# grizzly_bear_revF.net
KiCad netlist of a schematic drawn in EAGLE
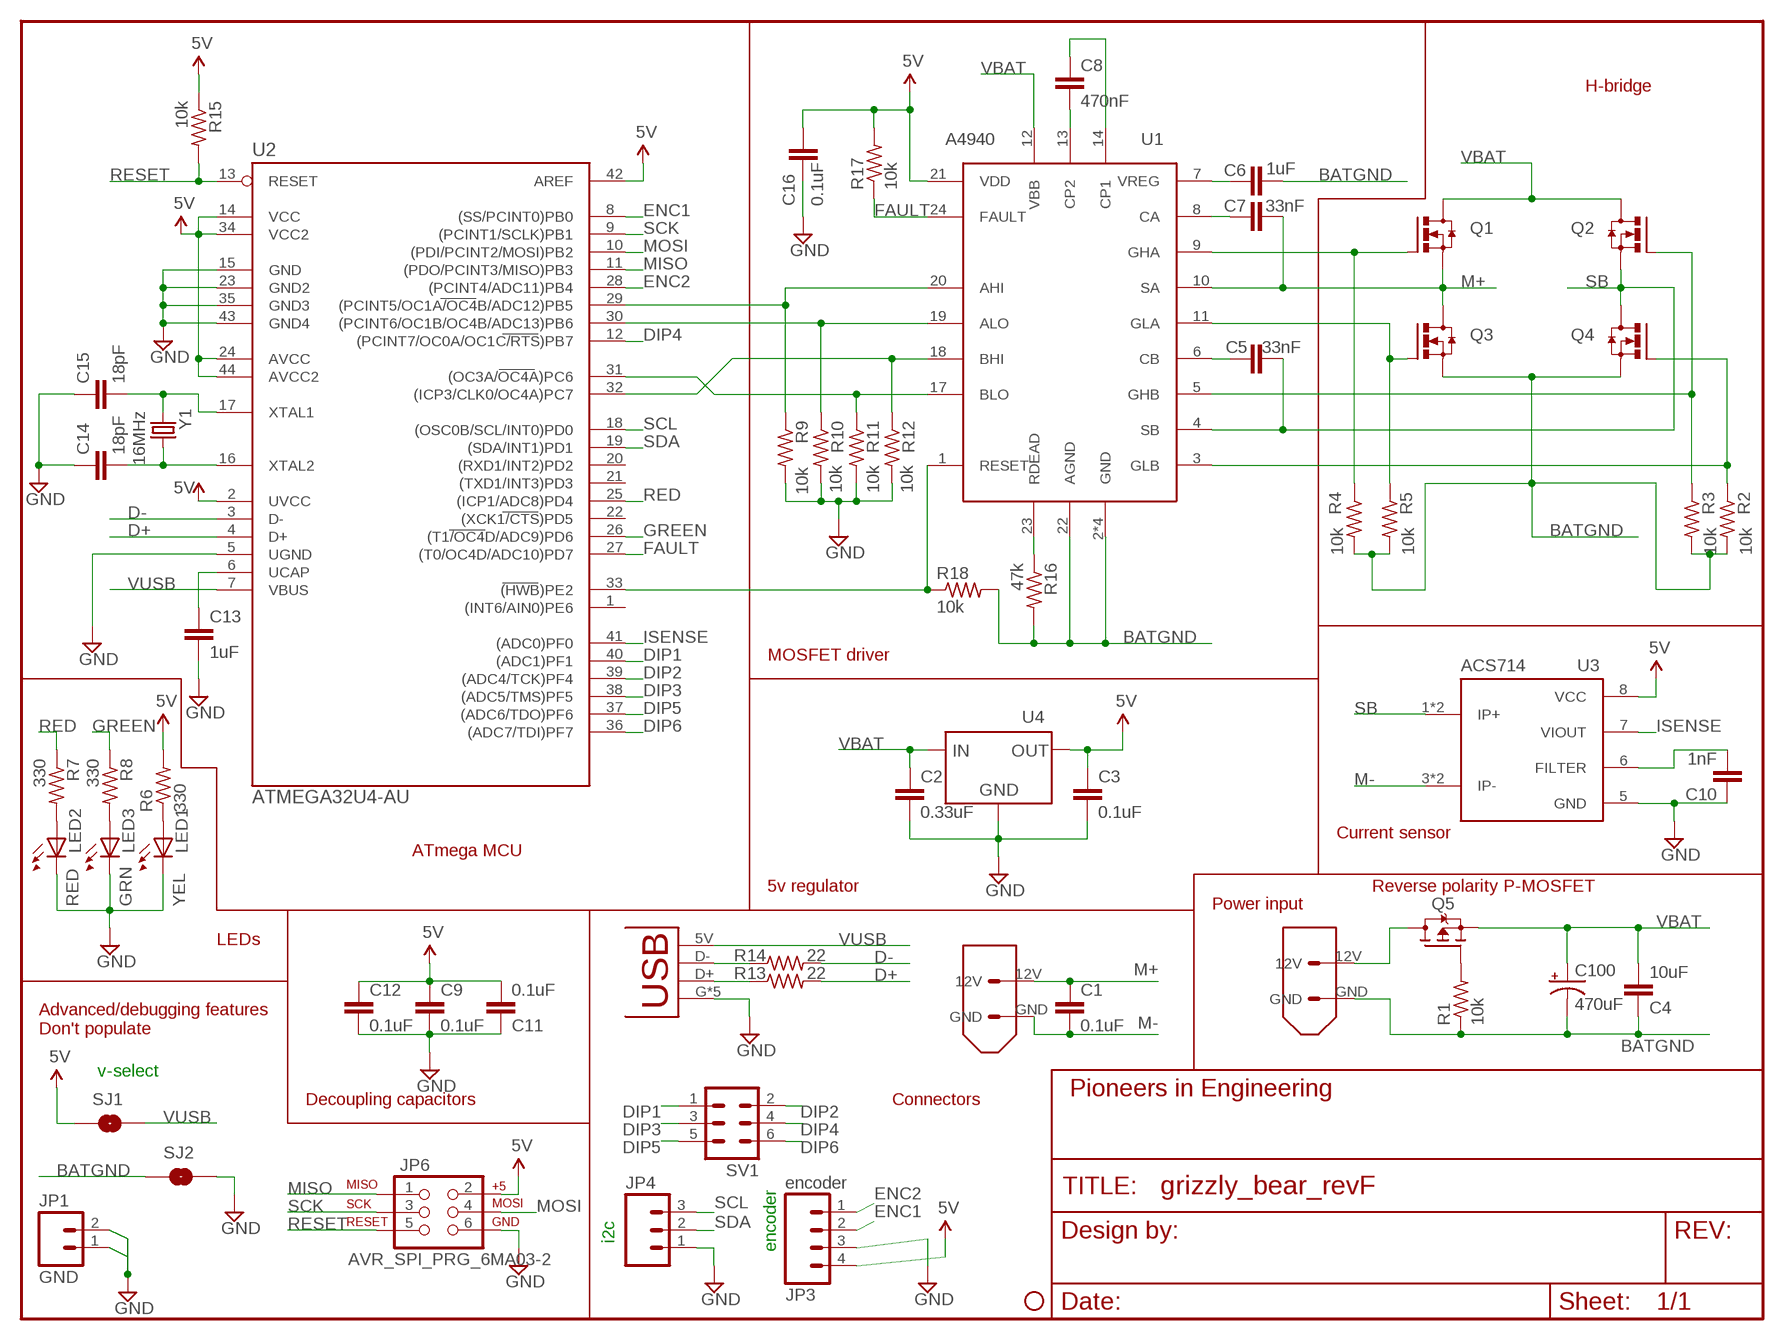
[diagram p0: schematic, sheet 1]

(export (version "E")
  (design (tool "Eeschema 10.0.6"))
  (components
    (comp (ref "C1")
      (value "0.1uF")
      (footprint "eagle-import:0603-CAP")
      (libsource (lib "eagle-import") (part "CAP0603-CAP"))
    )
    (comp (ref "C2")
      (value "0.33uF")
      (footprint "eagle-import:0603-CAP")
      (libsource (lib "eagle-import") (part "CAP0603-CAP"))
    )
    (comp (ref "C3")
      (value "0.1uF")
      (footprint "eagle-import:0603-CAP")
      (libsource (lib "eagle-import") (part "CAP0603-CAP"))
    )
    (comp (ref "C4")
      (value "10uF")
      (footprint "eagle-import:0603-CAP")
      (libsource (lib "eagle-import") (part "CAP0603-CAP"))
    )
    (comp (ref "C5")
      (value "33nF")
      (footprint "eagle-import:0603-CAP")
      (libsource (lib "eagle-import") (part "CAP0603-CAP"))
    )
    (comp (ref "C6")
      (value "1uF")
      (footprint "eagle-import:0603-CAP")
      (libsource (lib "eagle-import") (part "CAP0603-CAP"))
    )
    (comp (ref "C7")
      (value "33nF")
      (footprint "eagle-import:0603-CAP")
      (libsource (lib "eagle-import") (part "CAP0603-CAP"))
    )
    (comp (ref "C8")
      (value "470nF")
      (footprint "eagle-import:0603-CAP")
      (libsource (lib "eagle-import") (part "CAP0603-CAP"))
    )
    (comp (ref "C9")
      (value "0.1uF")
      (footprint "eagle-import:0603-CAP")
      (libsource (lib "eagle-import") (part "CAP0603-CAP"))
    )
    (comp (ref "C10")
      (value "1nF")
      (footprint "eagle-import:0603-CAP")
      (libsource (lib "eagle-import") (part "CAP0603-CAP"))
    )
    (comp (ref "C11")
      (value "0.1uF")
      (footprint "eagle-import:0603-CAP")
      (libsource (lib "eagle-import") (part "CAP0603-CAP"))
    )
    (comp (ref "C12")
      (value "0.1uF")
      (footprint "eagle-import:0603-CAP")
      (libsource (lib "eagle-import") (part "CAP0603-CAP"))
    )
    (comp (ref "C13")
      (value "1uF")
      (footprint "eagle-import:0603-CAP")
      (libsource (lib "eagle-import") (part "CAP0603-CAP"))
    )
    (comp (ref "C14")
      (value "18pF")
      (footprint "eagle-import:0603-CAP")
      (libsource (lib "eagle-import") (part "CAP0603-CAP"))
    )
    (comp (ref "C15")
      (value "18pF")
      (footprint "eagle-import:0603-CAP")
      (libsource (lib "eagle-import") (part "CAP0603-CAP"))
    )
    (comp (ref "C16")
      (value "0.1uF")
      (footprint "eagle-import:0603-CAP")
      (libsource (lib "eagle-import") (part "CAP0603-CAP"))
    )
    (comp (ref "C100")
      (value "470uF")
      (footprint "eagle-import:PANASONIC_G")
      (libsource (lib "eagle-import") (part "CAP_POLG"))
    )
    (comp (ref "JP1")
      (value "GND")
      (footprint "eagle-import:1X02")
      (libsource (lib "eagle-import") (part "M02PTH"))
    )
    (comp (ref "JP3")
      (value "encoder")
      (footprint "eagle-import:1X04-MTA")
      (fields (field (name "PARTNUMBER") "A1922-ND"))
      (libsource (lib "eagle-import") (part "M041X04-MTA"))
    )
    (comp (ref "JP4")
      (value "M031X03-MTA")
      (footprint "eagle-import:1X03-MTA")
      (fields (field (name "PARTNUMBER") "A19470-ND"))
      (libsource (lib "eagle-import") (part "M031X03-MTA"))
    )
    (comp (ref "JP6")
      (value "AVR_SPI_PRG_6MA03-2")
      (footprint "eagle-import:MA03-2")
      (libsource (lib "eagle-import") (part "AVR_SPI_PRG_6MA03-2"))
    )
    (comp (ref "LED1")
      (value "YEL")
      (footprint "eagle-import:LED-0805")
      (libsource (lib "eagle-import") (part "LED0805"))
    )
    (comp (ref "LED2")
      (value "RED")
      (footprint "eagle-import:LED-0805")
      (libsource (lib "eagle-import") (part "LED0805"))
    )
    (comp (ref "LED3")
      (value "GRN")
      (footprint "eagle-import:LED-0805")
      (libsource (lib "eagle-import") (part "LED0805"))
    )
    (comp (ref "Q1")
      (value "N-CHANNEL-MOSFET")
      (footprint "eagle-import:SOT669")
      (libsource (lib "eagle-import") (part "N-CHANNEL-MOSFET"))
    )
    (comp (ref "Q2")
      (value "N-CHANNEL-MOSFET")
      (footprint "eagle-import:SOT669")
      (libsource (lib "eagle-import") (part "N-CHANNEL-MOSFET"))
    )
    (comp (ref "Q3")
      (value "N-CHANNEL-MOSFET")
      (footprint "eagle-import:SOT669")
      (libsource (lib "eagle-import") (part "N-CHANNEL-MOSFET"))
    )
    (comp (ref "Q4")
      (value "N-CHANNEL-MOSFET")
      (footprint "eagle-import:SOT669")
      (libsource (lib "eagle-import") (part "N-CHANNEL-MOSFET"))
    )
    (comp (ref "Q5")
      (value "IPD90P03P4L")
      (footprint "eagle-import:TO252")
      (libsource (lib "eagle-import") (part "P-CHANNEL-MOSFETTO252"))
    )
    (comp (ref "R1")
      (value "10k")
      (footprint "eagle-import:R0603")
      (libsource (lib "eagle-import") (part "R-US_R0603"))
    )
    (comp (ref "R2")
      (value "10k")
      (footprint "eagle-import:R0603")
      (libsource (lib "eagle-import") (part "R-US_R0603"))
    )
    (comp (ref "R3")
      (value "10k")
      (footprint "eagle-import:R0603")
      (libsource (lib "eagle-import") (part "R-US_R0603"))
    )
    (comp (ref "R4")
      (value "10k")
      (footprint "eagle-import:R0603")
      (libsource (lib "eagle-import") (part "R-US_R0603"))
    )
    (comp (ref "R5")
      (value "10k")
      (footprint "eagle-import:R0603")
      (libsource (lib "eagle-import") (part "R-US_R0603"))
    )
    (comp (ref "R6")
      (value "330")
      (footprint "eagle-import:R0603")
      (libsource (lib "eagle-import") (part "R-US_R0603"))
    )
    (comp (ref "R7")
      (value "330")
      (footprint "eagle-import:R0603")
      (libsource (lib "eagle-import") (part "R-US_R0603"))
    )
    (comp (ref "R8")
      (value "330")
      (footprint "eagle-import:R0603")
      (libsource (lib "eagle-import") (part "R-US_R0603"))
    )
    (comp (ref "R9")
      (value "10k")
      (footprint "eagle-import:R0603")
      (libsource (lib "eagle-import") (part "R-US_R0603"))
    )
    (comp (ref "R10")
      (value "10k")
      (footprint "eagle-import:R0603")
      (libsource (lib "eagle-import") (part "R-US_R0603"))
    )
    (comp (ref "R11")
      (value "10k")
      (footprint "eagle-import:R0603")
      (libsource (lib "eagle-import") (part "R-US_R0603"))
    )
    (comp (ref "R12")
      (value "10k")
      (footprint "eagle-import:R0603")
      (libsource (lib "eagle-import") (part "R-US_R0603"))
    )
    (comp (ref "R13")
      (value "22")
      (footprint "eagle-import:R0603")
      (libsource (lib "eagle-import") (part "R-US_R0603"))
    )
    (comp (ref "R14")
      (value "22")
      (footprint "eagle-import:R0603")
      (libsource (lib "eagle-import") (part "R-US_R0603"))
    )
    (comp (ref "R15")
      (value "10k")
      (footprint "eagle-import:R0603")
      (libsource (lib "eagle-import") (part "R-US_R0603"))
    )
    (comp (ref "R16")
      (value "47k")
      (footprint "eagle-import:R0603")
      (libsource (lib "eagle-import") (part "R-US_R0603"))
    )
    (comp (ref "R17")
      (value "10k")
      (footprint "eagle-import:R0603")
      (libsource (lib "eagle-import") (part "R-US_R0603"))
    )
    (comp (ref "R18")
      (value "10k")
      (footprint "eagle-import:R0603")
      (libsource (lib "eagle-import") (part "R-US_R0603"))
    )
    (comp (ref "SJ1")
      (value "SOLDERJUMPERNO")
      (footprint "eagle-import:SJ_2S-NO")
      (libsource (lib "eagle-import") (part "SOLDERJUMPERNO"))
    )
    (comp (ref "SJ2")
      (value "SOLDERJUMPERNO")
      (footprint "eagle-import:SJ_2S-NO")
      (libsource (lib "eagle-import") (part "SOLDERJUMPERNO"))
    )
    (comp (ref "STANDOFF4")
      (value "STAND-OFF")
      (footprint "eagle-import:STAND-OFF")
      (libsource (lib "eagle-import") (part "STAND-OFF"))
    )
    (comp (ref "SV1")
      (value "MA03-2")
      (footprint "eagle-import:MA03-2")
      (libsource (lib "eagle-import") (part "MA03-2"))
    )
    (comp (ref "U$2")
      (value "USB-M26FTR")
      (footprint "eagle-import:USB-M26FTR")
      (libsource (lib "eagle-import") (part "USB-M26FTR"))
    )
    (comp (ref "U$18")
      (value "XT60CONNECTOR")
      (footprint "eagle-import:XT60CONNECTOR")
      (fields (field (name "PARTNUMBER") "PRT-10474 "))
      (libsource (lib "eagle-import") (part "XT60CONNECTOR"))
    )
    (comp (ref "U$19")
      (value "XT60CONNECTOR")
      (footprint "eagle-import:XT60CONNECTOR")
      (fields (field (name "PARTNUMBER") "PRT-10474 "))
      (libsource (lib "eagle-import") (part "XT60CONNECTOR"))
    )
    (comp (ref "U1")
      (value "A4940")
      (footprint "eagle-import:24-PIN_TSSOP")
      (libsource (lib "eagle-import") (part "A4940"))
    )
    (comp (ref "U2")
      (value "ATMEGA32U4-AU")
      (footprint "eagle-import:TQFP44")
      (libsource (lib "eagle-import") (part "ATMEGA32U4-AU"))
    )
    (comp (ref "U3")
      (value "ACS714")
      (footprint "eagle-import:8-PIN_SOIC")
      (libsource (lib "eagle-import") (part "ACS714"))
    )
    (comp (ref "U4")
      (value "UA78L00")
      (footprint "eagle-import:SOT-89-3")
      (libsource (lib "eagle-import") (part "UA78L00"))
    )
    (comp (ref "Y1")
      (value "16MHz")
      (footprint "eagle-import:HC49UP")
      (libsource (lib "eagle-import") (part "CRYSTALSMD"))
    )
  )
  (nets
    (net (code "1") (name "/BATGND") (class "Default")
      (node (ref "C100") (pin "-") (pinfunction "-_-") (pintype "passive"))
      (node (ref "C4") (pin "1") (pinfunction "1_1") (pintype "passive"))
      (node (ref "C6") (pin "2") (pinfunction "2_2") (pintype "passive"))
      (node (ref "Q3") (pin "1") (pinfunction "S_1") (pintype "passive"))
      (node (ref "Q3") (pin "2") (pinfunction "S_2") (pintype "passive"))
      (node (ref "Q3") (pin "3") (pinfunction "S_3") (pintype "passive"))
      (node (ref "Q4") (pin "1") (pinfunction "S_1") (pintype "passive"))
      (node (ref "Q4") (pin "2") (pinfunction "S_2") (pintype "passive"))
      (node (ref "Q4") (pin "3") (pinfunction "S_3") (pintype "passive"))
      (node (ref "R1") (pin "1") (pinfunction "1_1") (pintype "passive"))
      (node (ref "R16") (pin "2") (pinfunction "2_2") (pintype "passive"))
      (node (ref "R18") (pin "2") (pinfunction "2_2") (pintype "passive"))
      (node (ref "R2") (pin "2") (pinfunction "2_2") (pintype "passive"))
      (node (ref "R3") (pin "2") (pinfunction "2_2") (pintype "passive"))
      (node (ref "R4") (pin "2") (pinfunction "2_2") (pintype "passive"))
      (node (ref "R5") (pin "2") (pinfunction "2_2") (pintype "passive"))
      (node (ref "SJ2") (pin "1") (pinfunction "1_1") (pintype "passive"))
      (node (ref "U$18") (pin "GND") (pinfunction "GND_GND") (pintype "bidirectional"))
      (node (ref "U1") (pin "15") (pinfunction "GND_15") (pintype "bidirectional"))
      (node (ref "U1") (pin "16") (pinfunction "GND_16") (pintype "bidirectional"))
      (node (ref "U1") (pin "2") (pinfunction "GND_2") (pintype "bidirectional"))
      (node (ref "U1") (pin "22") (pinfunction "AGND_22") (pintype "bidirectional"))
      (node (ref "U1") (pin "PAD") (pinfunction "GND_PAD") (pintype "bidirectional"))
    )
    (net (code "2") (name "/D+") (class "Default")
      (node (ref "R13") (pin "2") (pinfunction "2_2") (pintype "passive"))
      (node (ref "U2") (pin "4") (pinfunction "D+_4") (pintype "bidirectional"))
    )
    (net (code "3") (name "/D-") (class "Default")
      (node (ref "R14") (pin "2") (pinfunction "2_2") (pintype "passive"))
      (node (ref "U2") (pin "3") (pinfunction "D-_3") (pintype "bidirectional"))
    )
    (net (code "4") (name "/DIP1") (class "Default")
      (node (ref "SV1") (pin "1") (pinfunction "1_1") (pintype "passive"))
      (node (ref "U2") (pin "40") (pinfunction "(ADC1)PF1_40") (pintype "bidirectional"))
    )
    (net (code "5") (name "/DIP2") (class "Default")
      (node (ref "SV1") (pin "2") (pinfunction "2_2") (pintype "passive"))
      (node (ref "U2") (pin "39") (pinfunction "(ADC4/TCK)PF4_39") (pintype "bidirectional"))
    )
    (net (code "6") (name "/DIP3") (class "Default")
      (node (ref "SV1") (pin "3") (pinfunction "3_3") (pintype "passive"))
      (node (ref "U2") (pin "38") (pinfunction "(ADC5/TMS)PF5_38") (pintype "bidirectional"))
    )
    (net (code "7") (name "/DIP4") (class "Default")
      (node (ref "SV1") (pin "4") (pinfunction "4_4") (pintype "passive"))
      (node (ref "U2") (pin "12") (pinfunction "(PCINT7/OC0A/OC1C/RTS)PB7_12") (pintype "bidirectional"))
    )
    (net (code "8") (name "/DIP5") (class "Default")
      (node (ref "SV1") (pin "5") (pinfunction "5_5") (pintype "passive"))
      (node (ref "U2") (pin "37") (pinfunction "(ADC6/TDO)PF6_37") (pintype "bidirectional"))
    )
    (net (code "9") (name "/DIP6") (class "Default")
      (node (ref "SV1") (pin "6") (pinfunction "6_6") (pintype "passive"))
      (node (ref "U2") (pin "36") (pinfunction "(ADC7/TDI)PF7_36") (pintype "bidirectional"))
    )
    (net (code "10") (name "/ENC1") (class "Default")
      (node (ref "JP3") (pin "2") (pinfunction "2_2") (pintype "passive"))
      (node (ref "U2") (pin "8") (pinfunction "(SS/PCINT0)PB0_8") (pintype "bidirectional"))
    )
    (net (code "11") (name "/ENC2") (class "Default")
      (node (ref "JP3") (pin "1") (pinfunction "1_1") (pintype "passive"))
      (node (ref "U2") (pin "28") (pinfunction "(PCINT4/ADC11)PB4_28") (pintype "bidirectional"))
    )
    (net (code "12") (name "/FAULT") (class "Default")
      (node (ref "R17") (pin "1") (pinfunction "1_1") (pintype "passive"))
      (node (ref "U1") (pin "24") (pinfunction "FAULT_24") (pintype "bidirectional"))
      (node (ref "U2") (pin "27") (pinfunction "(T0/OC4D/ADC10)PD7_27") (pintype "bidirectional"))
    )
    (net (code "13") (name "/GREEN") (class "Default")
      (node (ref "R8") (pin "1") (pinfunction "1_1") (pintype "passive"))
      (node (ref "U2") (pin "26") (pinfunction "(T1/OC4D/ADC9)PD6_26") (pintype "bidirectional"))
    )
    (net (code "14") (name "/ISENSE") (class "Default")
      (node (ref "U2") (pin "41") (pinfunction "(ADC0)PF0_41") (pintype "bidirectional"))
      (node (ref "U3") (pin "7") (pinfunction "VIOUT_7") (pintype "bidirectional"))
    )
    (net (code "15") (name "/M+") (class "Default")
      (node (ref "C1") (pin "1") (pinfunction "1_1") (pintype "passive"))
      (node (ref "C7") (pin "2") (pinfunction "2_2") (pintype "passive"))
      (node (ref "Q1") (pin "1") (pinfunction "S_1") (pintype "passive"))
      (node (ref "Q1") (pin "2") (pinfunction "S_2") (pintype "passive"))
      (node (ref "Q1") (pin "3") (pinfunction "S_3") (pintype "passive"))
      (node (ref "Q3") (pin "MB") (pinfunction "D_MB") (pintype "passive"))
      (node (ref "U$19") (pin "12V") (pinfunction "12V_12V") (pintype "bidirectional"))
      (node (ref "U1") (pin "10") (pinfunction "SA_10") (pintype "bidirectional"))
    )
    (net (code "16") (name "/M-") (class "Default")
      (node (ref "C1") (pin "2") (pinfunction "2_2") (pintype "passive"))
      (node (ref "U$19") (pin "GND") (pinfunction "GND_GND") (pintype "bidirectional"))
      (node (ref "U3") (pin "3") (pinfunction "IP-_3") (pintype "bidirectional"))
      (node (ref "U3") (pin "4") (pinfunction "IP-_4") (pintype "bidirectional"))
    )
    (net (code "17") (name "/MISO") (class "Default")
      (node (ref "JP6") (pin "1") (pinfunction "1_1") (pintype "passive"))
      (node (ref "U2") (pin "11") (pinfunction "(PDO/PCINT3/MISO)PB3_11") (pintype "bidirectional"))
    )
    (net (code "18") (name "/MOSI") (class "Default")
      (node (ref "JP6") (pin "4") (pinfunction "4_4") (pintype "passive"))
      (node (ref "U2") (pin "10") (pinfunction "(PDI/PCINT2/MOSI)PB2_10") (pintype "bidirectional"))
    )
    (net (code "19") (name "/RED") (class "Default")
      (node (ref "R7") (pin "1") (pinfunction "1_1") (pintype "passive"))
      (node (ref "U2") (pin "25") (pinfunction "(ICP1/ADC8)PD4_25") (pintype "bidirectional"))
    )
    (net (code "20") (name "/RESET") (class "Default")
      (node (ref "JP6") (pin "5") (pinfunction "5_5") (pintype "passive"))
      (node (ref "R15") (pin "2") (pinfunction "2_2") (pintype "passive"))
      (node (ref "U2") (pin "13") (pinfunction "RESET_13") (pintype "bidirectional"))
    )
    (net (code "21") (name "/SB") (class "Default")
      (node (ref "C5") (pin "1") (pinfunction "1_1") (pintype "passive"))
      (node (ref "Q2") (pin "1") (pinfunction "S_1") (pintype "passive"))
      (node (ref "Q2") (pin "2") (pinfunction "S_2") (pintype "passive"))
      (node (ref "Q2") (pin "3") (pinfunction "S_3") (pintype "passive"))
      (node (ref "Q4") (pin "MB") (pinfunction "D_MB") (pintype "passive"))
      (node (ref "U1") (pin "4") (pinfunction "SB_4") (pintype "bidirectional"))
      (node (ref "U3") (pin "1") (pinfunction "IP+_1") (pintype "bidirectional"))
      (node (ref "U3") (pin "2") (pinfunction "IP+_2") (pintype "bidirectional"))
    )
    (net (code "22") (name "/SCK") (class "Default")
      (node (ref "JP6") (pin "3") (pinfunction "3_3") (pintype "passive"))
      (node (ref "U2") (pin "9") (pinfunction "(PCINT1/SCLK)PB1_9") (pintype "bidirectional"))
    )
    (net (code "23") (name "/SCL") (class "Default")
      (node (ref "JP4") (pin "3") (pinfunction "3_3") (pintype "passive"))
      (node (ref "U2") (pin "18") (pinfunction "(OSC0B/SCL/INT0)PD0_18") (pintype "bidirectional"))
    )
    (net (code "24") (name "/SDA") (class "Default")
      (node (ref "JP4") (pin "2") (pinfunction "2_2") (pintype "passive"))
      (node (ref "U2") (pin "19") (pinfunction "(SDA/INT1)PD1_19") (pintype "bidirectional"))
    )
    (net (code "25") (name "/VBAT") (class "Default")
      (node (ref "C100") (pin "+") (pinfunction "+_+") (pintype "passive"))
      (node (ref "C2") (pin "1") (pinfunction "1_1") (pintype "passive"))
      (node (ref "C4") (pin "2") (pinfunction "2_2") (pintype "passive"))
      (node (ref "Q1") (pin "MB") (pinfunction "D_MB") (pintype "passive"))
      (node (ref "Q2") (pin "MB") (pinfunction "D_MB") (pintype "passive"))
      (node (ref "Q5") (pin "2") (pinfunction "S_2") (pintype "passive"))
      (node (ref "U1") (pin "12") (pinfunction "VBB_12") (pintype "bidirectional"))
      (node (ref "U4") (pin "INPUT") (pinfunction "IN_INPUT") (pintype "bidirectional"))
    )
    (net (code "26") (name "/VUSB") (class "Default")
      (node (ref "SJ1") (pin "2") (pinfunction "2_2") (pintype "passive"))
      (node (ref "U$2") (pin "5V") (pinfunction "5V_5V") (pintype "bidirectional"))
      (node (ref "U2") (pin "7") (pinfunction "VBUS_7") (pintype "bidirectional"))
    )
    (net (code "27") (name "5V") (class "Default")
      (node (ref "C11") (pin "2") (pinfunction "2_2") (pintype "passive"))
      (node (ref "C12") (pin "1") (pinfunction "1_1") (pintype "passive"))
      (node (ref "C16") (pin "1") (pinfunction "1_1") (pintype "passive"))
      (node (ref "C3") (pin "1") (pinfunction "1_1") (pintype "passive"))
      (node (ref "C9") (pin "1") (pinfunction "1_1") (pintype "passive"))
      (node (ref "JP3") (pin "4") (pinfunction "4_4") (pintype "passive"))
      (node (ref "JP6") (pin "2") (pinfunction "2_2") (pintype "passive"))
      (node (ref "R15") (pin "1") (pinfunction "1_1") (pintype "passive"))
      (node (ref "R17") (pin "2") (pinfunction "2_2") (pintype "passive"))
      (node (ref "R6") (pin "2") (pinfunction "2_2") (pintype "passive"))
      (node (ref "SJ1") (pin "1") (pinfunction "1_1") (pintype "passive"))
      (node (ref "U1") (pin "21") (pinfunction "VDD_21") (pintype "bidirectional"))
      (node (ref "U2") (pin "14") (pinfunction "VCC_14") (pintype "bidirectional"))
      (node (ref "U2") (pin "2") (pinfunction "UVCC_2") (pintype "bidirectional"))
      (node (ref "U2") (pin "24") (pinfunction "AVCC_24") (pintype "bidirectional"))
      (node (ref "U2") (pin "34") (pinfunction "VCC2_34") (pintype "bidirectional"))
      (node (ref "U2") (pin "42") (pinfunction "AREF_42") (pintype "bidirectional"))
      (node (ref "U2") (pin "44") (pinfunction "AVCC2_44") (pintype "bidirectional"))
      (node (ref "U3") (pin "8") (pinfunction "VCC_8") (pintype "bidirectional"))
      (node (ref "U4") (pin "OUTPUT") (pinfunction "OUT_OUTPUT") (pintype "bidirectional"))
    )
    (net (code "28") (name "GND") (class "Default")
      (node (ref "C10") (pin "1") (pinfunction "1_1") (pintype "passive"))
      (node (ref "C11") (pin "1") (pinfunction "1_1") (pintype "passive"))
      (node (ref "C12") (pin "2") (pinfunction "2_2") (pintype "passive"))
      (node (ref "C13") (pin "2") (pinfunction "2_2") (pintype "passive"))
      (node (ref "C14") (pin "1") (pinfunction "1_1") (pintype "passive"))
      (node (ref "C15") (pin "1") (pinfunction "1_1") (pintype "passive"))
      (node (ref "C16") (pin "2") (pinfunction "2_2") (pintype "passive"))
      (node (ref "C2") (pin "2") (pinfunction "2_2") (pintype "passive"))
      (node (ref "C3") (pin "2") (pinfunction "2_2") (pintype "passive"))
      (node (ref "C9") (pin "2") (pinfunction "2_2") (pintype "passive"))
      (node (ref "JP1") (pin "1") (pinfunction "1_1") (pintype "passive"))
      (node (ref "JP1") (pin "2") (pinfunction "2_2") (pintype "passive"))
      (node (ref "JP3") (pin "3") (pinfunction "3_3") (pintype "passive"))
      (node (ref "JP4") (pin "1") (pinfunction "1_1") (pintype "passive"))
      (node (ref "JP6") (pin "6") (pinfunction "6_6") (pintype "passive"))
      (node (ref "LED1") (pin "C") (pinfunction "C_C") (pintype "passive"))
      (node (ref "LED2") (pin "C") (pinfunction "C_C") (pintype "passive"))
      (node (ref "LED3") (pin "C") (pinfunction "C_C") (pintype "passive"))
      (node (ref "R10") (pin "2") (pinfunction "2_2") (pintype "passive"))
      (node (ref "R11") (pin "2") (pinfunction "2_2") (pintype "passive"))
      (node (ref "R12") (pin "2") (pinfunction "2_2") (pintype "passive"))
      (node (ref "R9") (pin "2") (pinfunction "2_2") (pintype "passive"))
      (node (ref "SJ2") (pin "2") (pinfunction "2_2") (pintype "passive"))
      (node (ref "U$2") (pin "G") (pinfunction "G_G") (pintype "bidirectional"))
      (node (ref "U$2") (pin "S1") (pinfunction "G_S1") (pintype "bidirectional"))
      (node (ref "U$2") (pin "S2") (pinfunction "G_S2") (pintype "bidirectional"))
      (node (ref "U$2") (pin "S3") (pinfunction "G_S3") (pintype "bidirectional"))
      (node (ref "U$2") (pin "S4") (pinfunction "G_S4") (pintype "bidirectional"))
      (node (ref "U2") (pin "15") (pinfunction "GND_15") (pintype "bidirectional"))
      (node (ref "U2") (pin "23") (pinfunction "GND2_23") (pintype "bidirectional"))
      (node (ref "U2") (pin "35") (pinfunction "GND3_35") (pintype "bidirectional"))
      (node (ref "U2") (pin "43") (pinfunction "GND4_43") (pintype "bidirectional"))
      (node (ref "U2") (pin "5") (pinfunction "UGND_5") (pintype "bidirectional"))
      (node (ref "U3") (pin "5") (pinfunction "GND_5") (pintype "bidirectional"))
      (node (ref "U4") (pin "COMMON") (pinfunction "GND_COMMON") (pintype "bidirectional"))
    )
    (net (code "29") (name "Net-(LED1-PadA)") (class "Default")
      (node (ref "LED1") (pin "A") (pinfunction "A_A") (pintype "passive"))
      (node (ref "R6") (pin "1") (pinfunction "1_1") (pintype "passive"))
    )
    (net (code "30") (name "Net-(LED2-PadA)") (class "Default")
      (node (ref "LED2") (pin "A") (pinfunction "A_A") (pintype "passive"))
      (node (ref "R7") (pin "2") (pinfunction "2_2") (pintype "passive"))
    )
    (net (code "31") (name "Net-(LED3-PadA)") (class "Default")
      (node (ref "LED3") (pin "A") (pinfunction "A_A") (pintype "passive"))
      (node (ref "R8") (pin "2") (pinfunction "2_2") (pintype "passive"))
    )
    (net (code "32") (name "Net-(Q1-G)") (class "Default")
      (node (ref "Q1") (pin "4") (pinfunction "G_4") (pintype "passive"))
      (node (ref "R4") (pin "1") (pinfunction "1_1") (pintype "passive"))
      (node (ref "U1") (pin "9") (pinfunction "GHA_9") (pintype "bidirectional"))
    )
    (net (code "33") (name "Net-(Q2-G)") (class "Default")
      (node (ref "Q2") (pin "4") (pinfunction "G_4") (pintype "passive"))
      (node (ref "R3") (pin "1") (pinfunction "1_1") (pintype "passive"))
      (node (ref "U1") (pin "5") (pinfunction "GHB_5") (pintype "bidirectional"))
    )
    (net (code "34") (name "Net-(Q3-G)") (class "Default")
      (node (ref "Q3") (pin "4") (pinfunction "G_4") (pintype "passive"))
      (node (ref "R5") (pin "1") (pinfunction "1_1") (pintype "passive"))
      (node (ref "U1") (pin "11") (pinfunction "GLA_11") (pintype "bidirectional"))
    )
    (net (code "35") (name "Net-(Q4-G)") (class "Default")
      (node (ref "Q4") (pin "4") (pinfunction "G_4") (pintype "passive"))
      (node (ref "R2") (pin "1") (pinfunction "1_1") (pintype "passive"))
      (node (ref "U1") (pin "3") (pinfunction "GLB_3") (pintype "bidirectional"))
    )
    (net (code "36") (name "Net-(Q5-D)") (class "Default")
      (node (ref "Q5") (pin "3") (pinfunction "D_3") (pintype "passive"))
      (node (ref "U$18") (pin "12V") (pinfunction "12V_12V") (pintype "bidirectional"))
    )
    (net (code "37") (name "Net-(Q5-G)") (class "Default")
      (node (ref "Q5") (pin "1") (pinfunction "G_1") (pintype "passive"))
      (node (ref "R1") (pin "2") (pinfunction "2_2") (pintype "passive"))
    )
    (net (code "38") (name "Net-(R13-Pad1)") (class "Default")
      (node (ref "R13") (pin "1") (pinfunction "1_1") (pintype "passive"))
      (node (ref "U$2") (pin "D+") (pinfunction "D+_D+") (pintype "bidirectional"))
    )
    (net (code "39") (name "Net-(R14-Pad1)") (class "Default")
      (node (ref "R14") (pin "1") (pinfunction "1_1") (pintype "passive"))
      (node (ref "U$2") (pin "D-") (pinfunction "D-_D-") (pintype "bidirectional"))
    )
    (net (code "40") (name "Net-(U1-AHI)") (class "Default")
      (node (ref "R9") (pin "1") (pinfunction "1_1") (pintype "passive"))
      (node (ref "U1") (pin "20") (pinfunction "AHI_20") (pintype "bidirectional"))
      (node (ref "U2") (pin "29") (pinfunction "(PCINT5/OC1A/OC4B/ADC12)PB5_29") (pintype "bidirectional"))
    )
    (net (code "41") (name "Net-(U1-ALO)") (class "Default")
      (node (ref "R10") (pin "1") (pinfunction "1_1") (pintype "passive"))
      (node (ref "U1") (pin "19") (pinfunction "ALO_19") (pintype "bidirectional"))
      (node (ref "U2") (pin "30") (pinfunction "(PCINT6/OC1B/OC4B/ADC13)PB6_30") (pintype "bidirectional"))
    )
    (net (code "42") (name "Net-(U1-BHI)") (class "Default")
      (node (ref "R12") (pin "1") (pinfunction "1_1") (pintype "passive"))
      (node (ref "U1") (pin "18") (pinfunction "BHI_18") (pintype "bidirectional"))
      (node (ref "U2") (pin "32") (pinfunction "(ICP3/CLK0/OC4A)PC7_32") (pintype "bidirectional"))
    )
    (net (code "43") (name "Net-(U1-BLO)") (class "Default")
      (node (ref "R11") (pin "1") (pinfunction "1_1") (pintype "passive"))
      (node (ref "U1") (pin "17") (pinfunction "BLO_17") (pintype "bidirectional"))
      (node (ref "U2") (pin "31") (pinfunction "(OC3A/OC4A)PC6_31") (pintype "bidirectional"))
    )
    (net (code "44") (name "Net-(U1-CA)") (class "Default")
      (node (ref "C7") (pin "1") (pinfunction "1_1") (pintype "passive"))
      (node (ref "U1") (pin "8") (pinfunction "CA_8") (pintype "bidirectional"))
    )
    (net (code "45") (name "Net-(U1-CB)") (class "Default")
      (node (ref "C5") (pin "2") (pinfunction "2_2") (pintype "passive"))
      (node (ref "U1") (pin "6") (pinfunction "CB_6") (pintype "bidirectional"))
    )
    (net (code "46") (name "Net-(U1-CP1)") (class "Default")
      (node (ref "C8") (pin "1") (pinfunction "1_1") (pintype "passive"))
      (node (ref "U1") (pin "14") (pinfunction "CP1_14") (pintype "bidirectional"))
    )
    (net (code "47") (name "Net-(U1-CP2)") (class "Default")
      (node (ref "C8") (pin "2") (pinfunction "2_2") (pintype "passive"))
      (node (ref "U1") (pin "13") (pinfunction "CP2_13") (pintype "bidirectional"))
    )
    (net (code "48") (name "Net-(U1-RDEAD)") (class "Default")
      (node (ref "R16") (pin "1") (pinfunction "1_1") (pintype "passive"))
      (node (ref "U1") (pin "23") (pinfunction "RDEAD_23") (pintype "bidirectional"))
    )
    (net (code "49") (name "Net-(U1-RESET)") (class "Default")
      (node (ref "R18") (pin "1") (pinfunction "1_1") (pintype "passive"))
      (node (ref "U1") (pin "1") (pinfunction "RESET_1") (pintype "bidirectional"))
      (node (ref "U2") (pin "33") (pinfunction "(HWB)PE2_33") (pintype "bidirectional"))
    )
    (net (code "50") (name "Net-(U1-VREG)") (class "Default")
      (node (ref "C6") (pin "1") (pinfunction "1_1") (pintype "passive"))
      (node (ref "U1") (pin "7") (pinfunction "VREG_7") (pintype "bidirectional"))
    )
    (net (code "51") (name "Net-(U2-UCAP)") (class "Default")
      (node (ref "C13") (pin "1") (pinfunction "1_1") (pintype "passive"))
      (node (ref "U2") (pin "6") (pinfunction "UCAP_6") (pintype "bidirectional"))
    )
    (net (code "52") (name "Net-(U2-XTAL1)") (class "Default")
      (node (ref "C15") (pin "2") (pinfunction "2_2") (pintype "passive"))
      (node (ref "U2") (pin "17") (pinfunction "XTAL1_17") (pintype "bidirectional"))
      (node (ref "Y1") (pin "2") (pinfunction "2_2") (pintype "passive"))
    )
    (net (code "53") (name "Net-(U2-XTAL2)") (class "Default")
      (node (ref "C14") (pin "2") (pinfunction "2_2") (pintype "passive"))
      (node (ref "U2") (pin "16") (pinfunction "XTAL2_16") (pintype "bidirectional"))
      (node (ref "Y1") (pin "1") (pinfunction "1_1") (pintype "passive"))
    )
    (net (code "54") (name "Net-(U3-FILTER)") (class "Default")
      (node (ref "C10") (pin "2") (pinfunction "2_2") (pintype "passive"))
      (node (ref "U3") (pin "6") (pinfunction "FILTER_6") (pintype "bidirectional"))
    )
    (net (code "55") (name "unconnected-(U2-(INT6{slash}AIN0)PE6-Pad1)") (class "Default")
      (node (ref "U2") (pin "1") (pinfunction "(INT6/AIN0)PE6_1") (pintype "bidirectional"))
    )
    (net (code "56") (name "unconnected-(U2-(RXD1{slash}INT2)PD2-Pad20)") (class "Default")
      (node (ref "U2") (pin "20") (pinfunction "(RXD1/INT2)PD2_20") (pintype "bidirectional"))
    )
    (net (code "57") (name "unconnected-(U2-(TXD1{slash}INT3)PD3-Pad21)") (class "Default")
      (node (ref "U2") (pin "21") (pinfunction "(TXD1/INT3)PD3_21") (pintype "bidirectional"))
    )
    (net (code "58") (name "unconnected-(U2-(XCK1{slash}CTS)PD5-Pad22)") (class "Default")
      (node (ref "U2") (pin "22") (pinfunction "(XCK1/CTS)PD5_22") (pintype "bidirectional"))
    )
  )
)
